# power1.net
KiCad netlist of a schematic drawn in Altium Designer
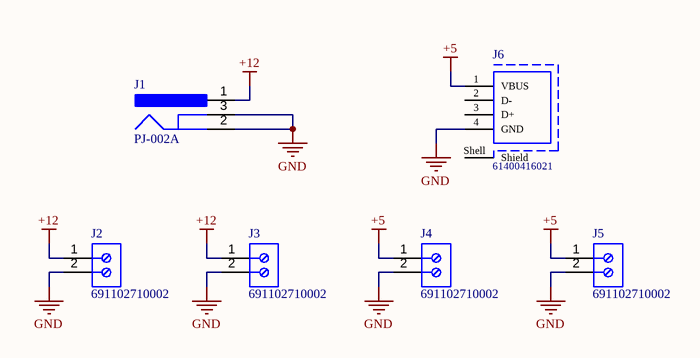
[diagram p0: power1.SchDoc]

(export (version "E")
  (design (tool "Eeschema 10.0.6"))
  (components
    (comp (ref "J1")
      (value "PJ-002A")
      (footprint "CUI-PJ-002A_V")
      (fields (field (name "MANUFACTURER") "CUIInc."))
      (libsource (lib "Altium Content Vault") (part "JACK-2CD3-RN_B"))
    )
    (comp (ref "J2")
      (value "691102710002")
      (footprint "691102710002")
      (description "Series 102 - 5.00 mm Horizontal Entry Modular with Pressure Clamp WR-TBL, 2 pin")
      (fields (field (name "MANUFACTURER") "Wurth Elektronik") (field (name "PUBLISHER") "WurthElektronik"))
      (libsource (lib "Altium Content Vault") (part "WE-CN-1P-F-TB2"))
    )
    (comp (ref "J3")
      (value "691102710002")
      (footprint "691102710002")
      (description "Series 102 - 5.00 mm Horizontal Entry Modular with Pressure Clamp WR-TBL, 2 pin")
      (fields (field (name "MANUFACTURER") "Wurth Elektronik") (field (name "PUBLISHER") "WurthElektronik"))
      (libsource (lib "Altium Content Vault") (part "WE-CN-1P-F-TB2"))
    )
    (comp (ref "J4")
      (value "691102710002")
      (footprint "691102710002")
      (description "Series 102 - 5.00 mm Horizontal Entry Modular with Pressure Clamp WR-TBL, 2 pin")
      (fields (field (name "MANUFACTURER") "Wurth Elektronik") (field (name "PUBLISHER") "WurthElektronik"))
      (libsource (lib "Altium Content Vault") (part "WE-CN-1P-F-TB2"))
    )
    (comp (ref "J5")
      (value "691102710002")
      (footprint "691102710002")
      (description "Series 102 - 5.00 mm Horizontal Entry Modular with Pressure Clamp WR-TBL, 2 pin")
      (fields (field (name "MANUFACTURER") "Wurth Elektronik") (field (name "PUBLISHER") "WurthElektronik"))
      (libsource (lib "Altium Content Vault") (part "WE-CN-1P-F-TB2"))
    )
    (comp (ref "J6")
      (value "61400416021")
      (footprint "61400416021")
      (description "USB 2.0 Type A Receptacle WR-COM, Horizontal, THT")
      (fields (field (name "MANUFACTURER") "Wurth Elektronik") (field (name "PUBLISHER") "WurthElektronik"))
      (libsource (lib "Altium Content Vault") (part "WE-USB-4-1SHLD"))
    )
  )
  (nets
    (net (code "1") (name "+5") (class "Default")
      (node (ref "J4") (pin "1") (pinfunction "1_1") (pintype "passive"))
      (node (ref "J5") (pin "1") (pinfunction "1_1") (pintype "passive"))
      (node (ref "J6") (pin "1") (pinfunction "VBUS_1") (pintype "passive"))
    )
    (net (code "2") (name "+12") (class "Default")
      (node (ref "J1") (pin "1") (pinfunction "1_1") (pintype "passive"))
      (node (ref "J2") (pin "1") (pinfunction "1_1") (pintype "passive"))
      (node (ref "J3") (pin "1") (pinfunction "1_1") (pintype "passive"))
    )
    (net (code "3") (name "GND") (class "Default")
      (node (ref "J1") (pin "2") (pinfunction "2_2") (pintype "passive"))
      (node (ref "J1") (pin "3") (pinfunction "3_3") (pintype "passive"))
      (node (ref "J2") (pin "2") (pinfunction "2_2") (pintype "passive"))
      (node (ref "J3") (pin "2") (pinfunction "2_2") (pintype "passive"))
      (node (ref "J4") (pin "2") (pinfunction "2_2") (pintype "passive"))
      (node (ref "J5") (pin "2") (pinfunction "2_2") (pintype "passive"))
      (node (ref "J6") (pin "4") (pinfunction "GND_4") (pintype "passive"))
    )
    (net (code "4") (name "unconnected-(J6-D+-Pad3)") (class "Default")
      (node (ref "J6") (pin "3") (pinfunction "D+_3") (pintype "passive"))
    )
    (net (code "5") (name "unconnected-(J6-D--Pad2)") (class "Default")
      (node (ref "J6") (pin "2") (pinfunction "D-_2") (pintype "passive"))
    )
    (net (code "6") (name "unconnected-(J6-Shield-PadShell)") (class "Default")
      (node (ref "J6") (pin "Shell") (pinfunction "Shield_Shell") (pintype "passive"))
    )
  )
)
